# ESP181A.net
KiCad netlist of a schematic drawn in EAGLE
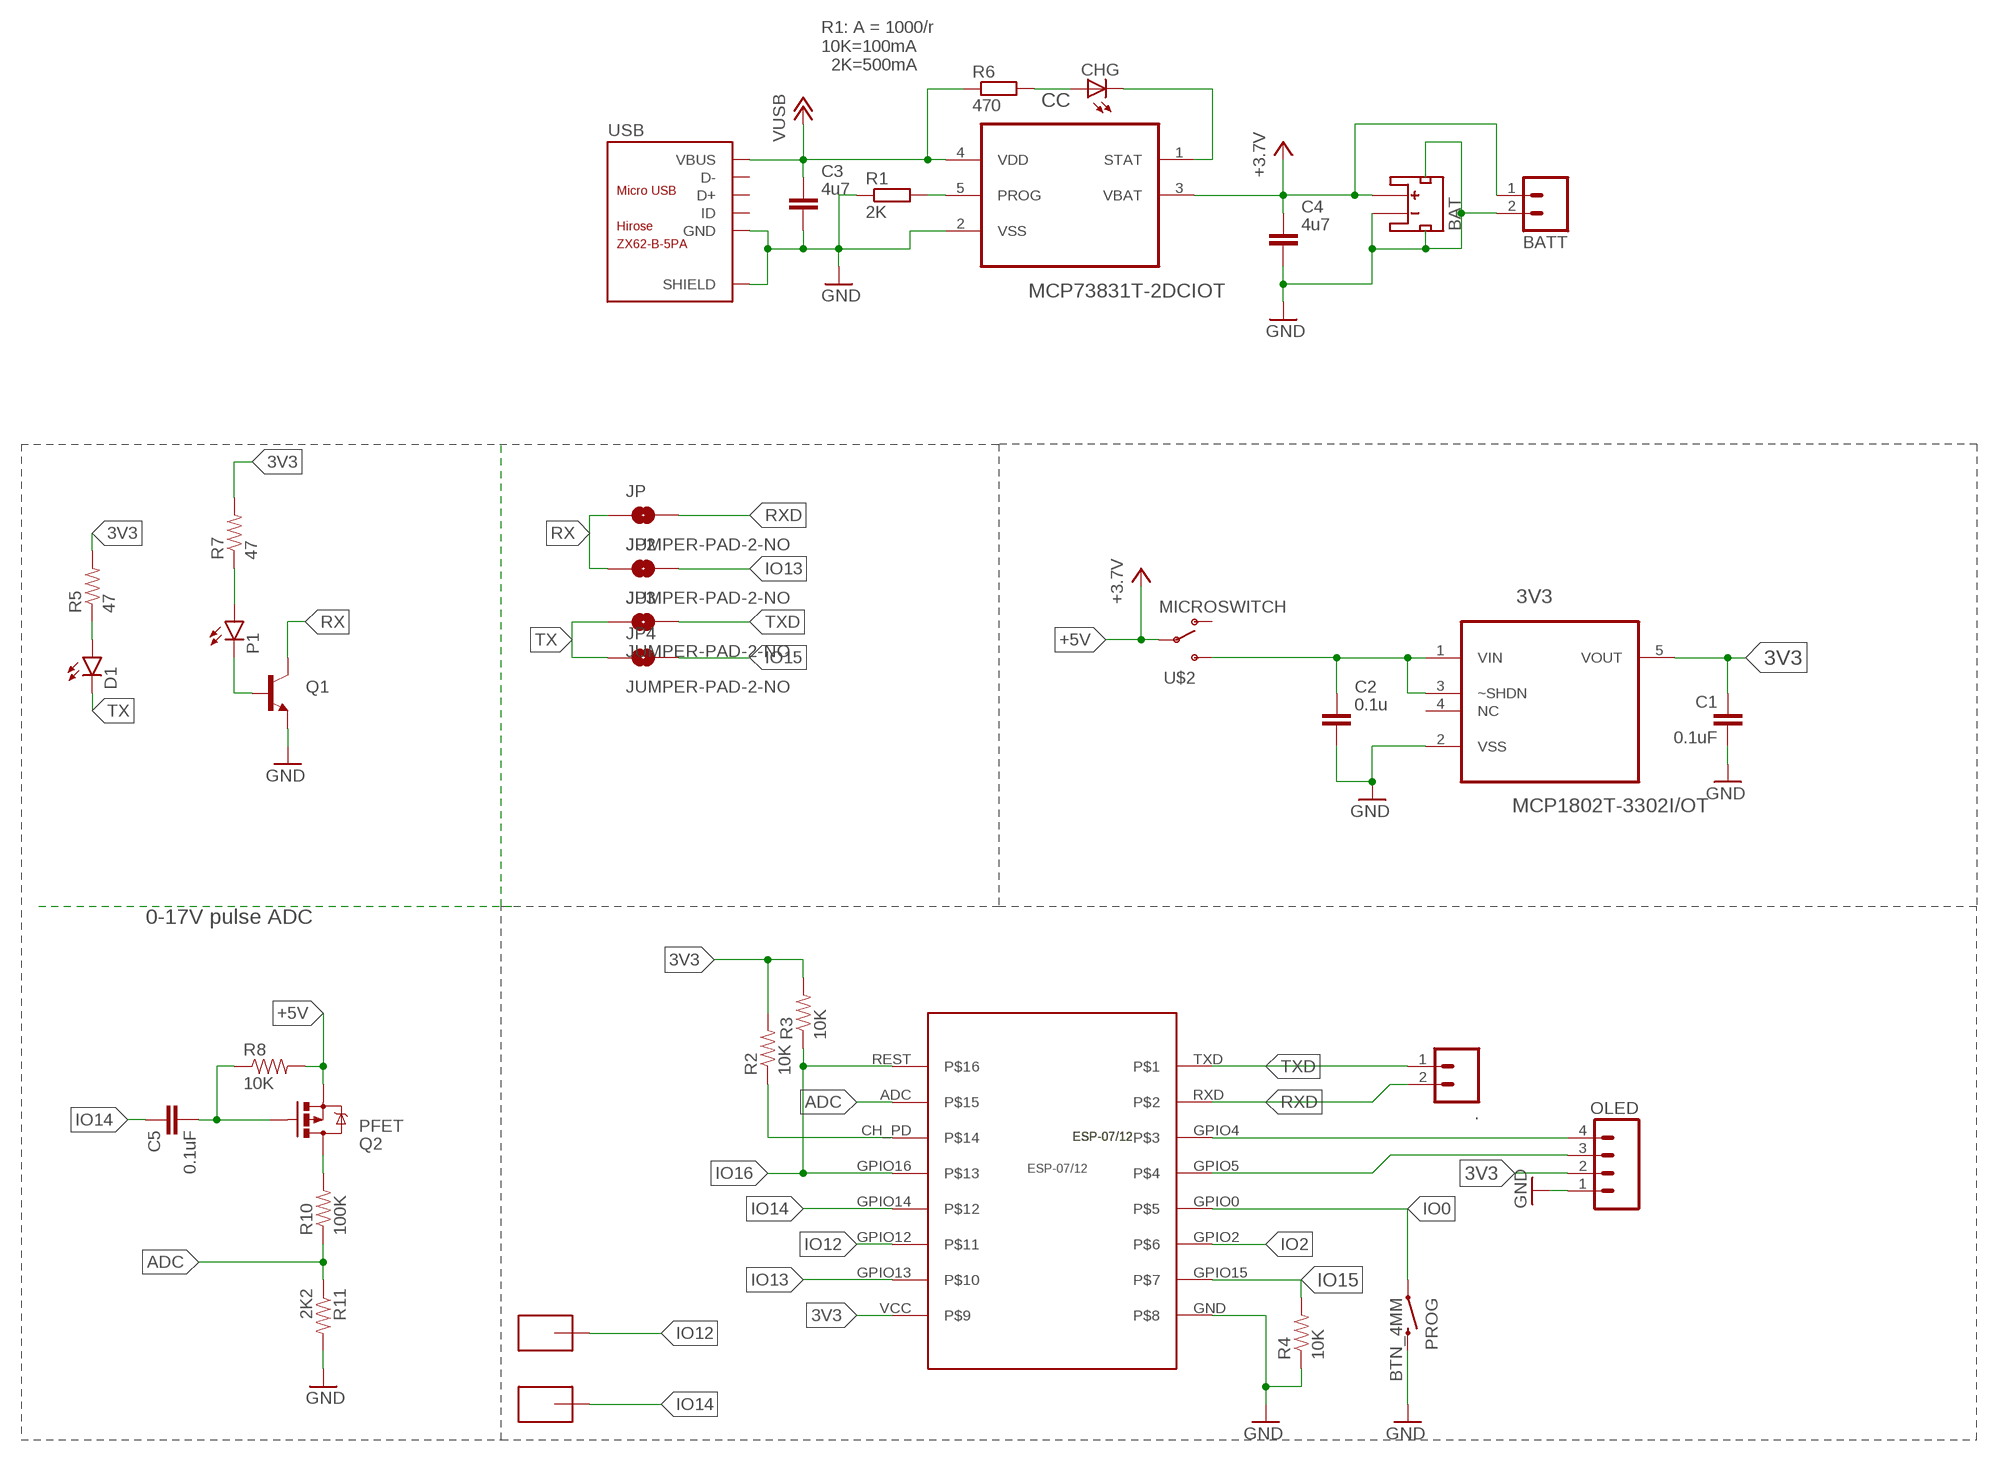
[diagram p0: schematic, sheet 1]

(export (version "E")
  (design (tool "Eeschema 10.0.6"))
  (components
    (comp (ref ".")
      (value "M02PTH")
      (footprint "eagle-import:1X02")
      (libsource (lib "eagle-import") (part "M02PTH"))
    )
    (comp (ref "3V3")
      (value "MCP1802T-3302I/OT")
      (footprint "eagle-import:SOT95P270X145-5N")
      (fields (field (name "MPN") "MCP1802T-3002I/OT"))
      (libsource (lib "eagle-import") (part "MCP1802T-3002I/OT"))
    )
    (comp (ref "BAT")
      (value "JST1.25MM")
      (footprint "eagle-import:JST_1.25MM")
      (libsource (lib "eagle-import") (part "JST1.25MM"))
    )
    (comp (ref "BATT")
      (value "M02PTH")
      (footprint "eagle-import:1X02")
      (libsource (lib "eagle-import") (part "M02PTH"))
    )
    (comp (ref "C1")
      (value "0.1uF")
      (footprint "eagle-import:0805-CAP")
      (libsource (lib "eagle-import") (part "CAP"))
    )
    (comp (ref "C2")
      (value "0.1u")
      (footprint "eagle-import:C603")
      (libsource (lib "eagle-import") (part "CAPACITOR_NPOL-0603"))
    )
    (comp (ref "C3")
      (value "4u7")
      (footprint "eagle-import:C603")
      (libsource (lib "eagle-import") (part "CAPACITOR_NPOL-0603"))
    )
    (comp (ref "C4")
      (value "4u7")
      (footprint "eagle-import:C603")
      (libsource (lib "eagle-import") (part "CAPACITOR_NPOL-0603"))
    )
    (comp (ref "C5")
      (value "0.1uF")
      (footprint "eagle-import:0805-CAP")
      (libsource (lib "eagle-import") (part "CAP"))
    )
    (comp (ref "CC")
      (value "MCP73831T-2DCIOT")
      (footprint "eagle-import:SOT95P280X145-5N")
      (fields (field (name "MPN") "MCP73832T-2ACI/OT"))
      (libsource (lib "eagle-import") (part "MCP73832T-2ACI/OT"))
    )
    (comp (ref "CHG")
      (value "LEDCHIP-LED0805")
      (footprint "eagle-import:CHIP-LED0805")
      (libsource (lib "eagle-import") (part "LEDCHIP-LED0805"))
    )
    (comp (ref "D1")
      (value "LED3MM")
      (footprint "eagle-import:LED3MM")
      (libsource (lib "eagle-import") (part "LED3MM"))
    )
    (comp (ref "JP")
      (value "JUMPER-PAD-2-NO")
      (footprint "eagle-import:PAD-JUMPER-2-NO_NO_SILK")
      (libsource (lib "eagle-import") (part "JUMPER-PAD-2-NO"))
    )
    (comp (ref "JP2")
      (value "JUMPER-PAD-2-NO")
      (footprint "eagle-import:PAD-JUMPER-2-NO_NO_SILK")
      (libsource (lib "eagle-import") (part "JUMPER-PAD-2-NO"))
    )
    (comp (ref "JP3")
      (value "JUMPER-PAD-2-NO")
      (footprint "eagle-import:PAD-JUMPER-2-NO_NO_SILK")
      (libsource (lib "eagle-import") (part "JUMPER-PAD-2-NO"))
    )
    (comp (ref "JP4")
      (value "JUMPER-PAD-2-NO")
      (footprint "eagle-import:PAD-JUMPER-2-NO_NO_SILK")
      (libsource (lib "eagle-import") (part "JUMPER-PAD-2-NO"))
    )
    (comp (ref "OLED")
      (value "M04PTH")
      (footprint "eagle-import:1X04")
      (libsource (lib "eagle-import") (part "M04PTH"))
    )
    (comp (ref "P1")
      (value "LED3MM")
      (footprint "eagle-import:LED3MM")
      (libsource (lib "eagle-import") (part "LED3MM"))
    )
    (comp (ref "PROG")
      (value "BTN_4MM")
      (footprint "eagle-import:BTN_4MM")
      (libsource (lib "eagle-import") (part "BTN_4MM"))
    )
    (comp (ref "Q1")
      (value "TRANSISTOR_NPNSOT23-3")
      (footprint "eagle-import:SOT23-3")
      (libsource (lib "eagle-import") (part "TRANSISTOR_NPNSOT23-3"))
    )
    (comp (ref "Q2")
      (value "PFET")
      (footprint "eagle-import:SOT23-3")
      (libsource (lib "eagle-import") (part "MOSFET-PCHANNEL"))
    )
    (comp (ref "R1")
      (value "2K")
      (footprint "eagle-import:R603")
      (libsource (lib "eagle-import") (part "RESISTOR-0603"))
    )
    (comp (ref "R2")
      (value "10K")
      (footprint "eagle-import:0805")
      (libsource (lib "eagle-import") (part "RESISTOR0805-RES"))
    )
    (comp (ref "R3")
      (value "10K")
      (footprint "eagle-import:0805")
      (libsource (lib "eagle-import") (part "RESISTOR0805-RES"))
    )
    (comp (ref "R4")
      (value "10K")
      (footprint "eagle-import:0805")
      (libsource (lib "eagle-import") (part "RESISTOR0805-RES"))
    )
    (comp (ref "R5")
      (value "47")
      (footprint "eagle-import:0805")
      (libsource (lib "eagle-import") (part "RESISTOR0805-RES"))
    )
    (comp (ref "R6")
      (value "470")
      (footprint "eagle-import:R603")
      (libsource (lib "eagle-import") (part "RESISTOR-0603"))
    )
    (comp (ref "R7")
      (value "47")
      (footprint "eagle-import:0805")
      (libsource (lib "eagle-import") (part "RESISTOR0805-RES"))
    )
    (comp (ref "R8")
      (value "10K")
      (footprint "eagle-import:0805")
      (libsource (lib "eagle-import") (part "RESISTOR0805-RES"))
    )
    (comp (ref "R10")
      (value "100K")
      (footprint "eagle-import:0805")
      (libsource (lib "eagle-import") (part "RESISTOR0805-RES"))
    )
    (comp (ref "R11")
      (value "2K2")
      (footprint "eagle-import:0805")
      (libsource (lib "eagle-import") (part "RESISTOR0805-RES"))
    )
    (comp (ref "U$1")
      (value "ESP-07/12")
      (footprint "eagle-import:ESP-07_12")
      (libsource (lib "eagle-import") (part "ESP-07/12"))
    )
    (comp (ref "U$2")
      (value "MICROSWITCH")
      (footprint "eagle-import:MICROSWITCH")
      (libsource (lib "eagle-import") (part "MICROSWITCH"))
    )
    (comp (ref "U$3")
      (value "SMD-PAD182X64")
      (footprint "eagle-import:SMD-PAD1")
      (libsource (lib "eagle-import") (part "SMD-PAD182X64"))
    )
    (comp (ref "U$4")
      (value "SMD-PAD182X64")
      (footprint "eagle-import:SMD-PAD1")
      (libsource (lib "eagle-import") (part "SMD-PAD182X64"))
    )
    (comp (ref "USB")
      (value "ZX62-B-5PA")
      (footprint "eagle-import:MICRO-USB5+6P-SMD-0.65-AB")
      (libsource (lib "eagle-import") (part "MICRO-USB-SMD(ZX62-B-5PA)"))
    )
  )
  (nets
    (net (code "1") (name "+5V") (class "Default")
      (node (ref "BAT") (pin "2") (pinfunction "+_2") (pintype "bidirectional"))
      (node (ref "BATT") (pin "1") (pinfunction "1_1") (pintype "passive"))
      (node (ref "C4") (pin "1") (pinfunction "1_1") (pintype "passive"))
      (node (ref "CC") (pin "3") (pinfunction "VBAT_3") (pintype "output"))
      (node (ref "Q2") (pin "2") (pinfunction "S_2") (pintype "passive"))
      (node (ref "R8") (pin "2") (pinfunction "2_2") (pintype "passive"))
      (node (ref "U$2") (pin "2") (pinfunction "P_2") (pintype "passive"))
    )
    (net (code "2") (name "3V3") (class "Default")
      (node (ref "3V3") (pin "5") (pinfunction "VOUT_5") (pintype "output"))
      (node (ref "C1") (pin "1") (pinfunction "1_1") (pintype "passive"))
      (node (ref "OLED") (pin "2") (pinfunction "2_2") (pintype "passive"))
      (node (ref "R2") (pin "2") (pinfunction "2_2") (pintype "passive"))
      (node (ref "R3") (pin "2") (pinfunction "2_2") (pintype "passive"))
      (node (ref "R5") (pin "2") (pinfunction "2_2") (pintype "passive"))
      (node (ref "R7") (pin "2") (pinfunction "2_2") (pintype "passive"))
      (node (ref "U$1") (pin "VCC") (pinfunction "P$9_VCC") (pintype "bidirectional"))
    )
    (net (code "3") (name "ADC") (class "Default")
      (node (ref "R10") (pin "1") (pinfunction "1_1") (pintype "passive"))
      (node (ref "R11") (pin "1") (pinfunction "1_1") (pintype "passive"))
      (node (ref "U$1") (pin "ADC") (pinfunction "P$15_ADC") (pintype "bidirectional"))
    )
    (net (code "4") (name "GND") (class "Default")
      (node (ref "3V3") (pin "2") (pinfunction "VSS_2") (pintype "passive"))
      (node (ref "BAT") (pin "1") (pinfunction "-_1") (pintype "bidirectional"))
      (node (ref "BAT") (pin "NC1") (pinfunction "PAD1_NC1") (pintype "bidirectional"))
      (node (ref "BAT") (pin "NC2") (pinfunction "PAD2_NC2") (pintype "bidirectional"))
      (node (ref "BATT") (pin "2") (pinfunction "2_2") (pintype "passive"))
      (node (ref "C1") (pin "2") (pinfunction "2_2") (pintype "passive"))
      (node (ref "C2") (pin "2") (pinfunction "2_2") (pintype "passive"))
      (node (ref "C3") (pin "2") (pinfunction "2_2") (pintype "passive"))
      (node (ref "C4") (pin "2") (pinfunction "2_2") (pintype "passive"))
      (node (ref "CC") (pin "2") (pinfunction "VSS_2") (pintype "power_in"))
      (node (ref "OLED") (pin "1") (pinfunction "1_1") (pintype "passive"))
      (node (ref "PROG") (pin "2") (pinfunction "2_2") (pintype "passive"))
      (node (ref "Q1") (pin "2") (pinfunction "E_2") (pintype "passive"))
      (node (ref "R1") (pin "1") (pinfunction "1_1") (pintype "passive"))
      (node (ref "R11") (pin "2") (pinfunction "2_2") (pintype "passive"))
      (node (ref "R4") (pin "1") (pinfunction "1_1") (pintype "passive"))
      (node (ref "U$1") (pin "GND") (pinfunction "P$8_GND") (pintype "bidirectional"))
      (node (ref "USB") (pin "5") (pinfunction "GND_5") (pintype "power_in"))
      (node (ref "USB") (pin "P1") (pinfunction "SHIELD_P1") (pintype "power_in"))
      (node (ref "USB") (pin "P2") (pinfunction "SHIELD_P2") (pintype "power_in"))
      (node (ref "USB") (pin "P3") (pinfunction "SHIELD_P3") (pintype "power_in"))
      (node (ref "USB") (pin "P4") (pinfunction "SHIELD_P4") (pintype "power_in"))
      (node (ref "USB") (pin "P5") (pinfunction "SHIELD_P5") (pintype "power_in"))
      (node (ref "USB") (pin "P6") (pinfunction "SHIELD_P6") (pintype "power_in"))
    )
    (net (code "5") (name "IO0") (class "Default")
      (node (ref "PROG") (pin "1") (pinfunction "1_1") (pintype "passive"))
      (node (ref "U$1") (pin "GPIO0") (pinfunction "P$5_GPIO0") (pintype "bidirectional"))
    )
    (net (code "6") (name "IO2") (class "Default")
      (node (ref "U$1") (pin "GPIO2") (pinfunction "P$6_GPIO2") (pintype "bidirectional"))
    )
    (net (code "7") (name "IO12") (class "Default")
      (node (ref "U$1") (pin "GPIO12") (pinfunction "P$11_GPIO12") (pintype "bidirectional"))
      (node (ref "U$4") (pin ">PAD") (pinfunction "P$1_>PAD") (pintype "bidirectional"))
    )
    (net (code "8") (name "IO13") (class "Default")
      (node (ref "JP2") (pin "2") (pinfunction "2_2") (pintype "passive"))
      (node (ref "U$1") (pin "GPIO13") (pinfunction "P$10_GPIO13") (pintype "bidirectional"))
    )
    (net (code "9") (name "IO14") (class "Default")
      (node (ref "C5") (pin "1") (pinfunction "1_1") (pintype "passive"))
      (node (ref "U$1") (pin "GPIO14") (pinfunction "P$12_GPIO14") (pintype "bidirectional"))
      (node (ref "U$3") (pin ">PAD") (pinfunction "P$1_>PAD") (pintype "bidirectional"))
    )
    (net (code "10") (name "IO15") (class "Default")
      (node (ref "JP4") (pin "2") (pinfunction "2_2") (pintype "passive"))
      (node (ref "R4") (pin "2") (pinfunction "2_2") (pintype "passive"))
      (node (ref "U$1") (pin "GPIO15") (pinfunction "P$7_GPIO15") (pintype "bidirectional"))
    )
    (net (code "11") (name "IO16") (class "Default")
      (node (ref "R3") (pin "1") (pinfunction "1_1") (pintype "passive"))
      (node (ref "U$1") (pin "GPIO16") (pinfunction "P$13_GPIO16") (pintype "bidirectional"))
      (node (ref "U$1") (pin "REST") (pinfunction "P$16_REST") (pintype "bidirectional"))
    )
    (net (code "12") (name "Net-(3V3-VIN)") (class "Default")
      (node (ref "3V3") (pin "1") (pinfunction "VIN_1") (pintype "power_in"))
      (node (ref "3V3") (pin "3") (pinfunction "~{SHDN}_3") (pintype "input"))
      (node (ref "C2") (pin "1") (pinfunction "1_1") (pintype "passive"))
      (node (ref "U$2") (pin "3") (pinfunction "S_3") (pintype "passive"))
    )
    (net (code "13") (name "Net-(CC-PROG)") (class "Default")
      (node (ref "CC") (pin "5") (pinfunction "PROG_5") (pintype "input"))
      (node (ref "R1") (pin "2") (pinfunction "2_2") (pintype "passive"))
    )
    (net (code "14") (name "Net-(CC-STAT)") (class "Default")
      (node (ref "CC") (pin "1") (pinfunction "STAT_1") (pintype "output"))
      (node (ref "CHG") (pin "C") (pinfunction "C_C") (pintype "passive"))
    )
    (net (code "15") (name "Net-(CHG-PadA)") (class "Default")
      (node (ref "CHG") (pin "A") (pinfunction "A_A") (pintype "passive"))
      (node (ref "R6") (pin "2") (pinfunction "2_2") (pintype "passive"))
    )
    (net (code "16") (name "Net-(D1-PadA)") (class "Default")
      (node (ref "D1") (pin "A") (pinfunction "A_A") (pintype "passive"))
      (node (ref "R5") (pin "1") (pinfunction "1_1") (pintype "passive"))
    )
    (net (code "17") (name "Net-(P1-C)") (class "Default")
      (node (ref "P1") (pin "K") (pinfunction "C_K") (pintype "passive"))
      (node (ref "Q1") (pin "1") (pinfunction "B_1") (pintype "passive"))
    )
    (net (code "18") (name "Net-(P1-PadA)") (class "Default")
      (node (ref "P1") (pin "A") (pinfunction "A_A") (pintype "passive"))
      (node (ref "R7") (pin "1") (pinfunction "1_1") (pintype "passive"))
    )
    (net (code "19") (name "Net-(Q2-D)") (class "Default")
      (node (ref "Q2") (pin "3") (pinfunction "D_3") (pintype "passive"))
      (node (ref "R10") (pin "2") (pinfunction "2_2") (pintype "passive"))
    )
    (net (code "20") (name "Net-(Q2-G)") (class "Default")
      (node (ref "C5") (pin "2") (pinfunction "2_2") (pintype "passive"))
      (node (ref "Q2") (pin "1") (pinfunction "G_1") (pintype "passive"))
      (node (ref "R8") (pin "1") (pinfunction "1_1") (pintype "passive"))
    )
    (net (code "21") (name "Net-(U$1-P$3)") (class "Default")
      (node (ref "OLED") (pin "4") (pinfunction "4_4") (pintype "passive"))
      (node (ref "U$1") (pin "GPIO4") (pinfunction "P$3_GPIO4") (pintype "bidirectional"))
    )
    (net (code "22") (name "Net-(U$1-P$4)") (class "Default")
      (node (ref "OLED") (pin "3") (pinfunction "3_3") (pintype "passive"))
      (node (ref "U$1") (pin "GPIO5") (pinfunction "P$4_GPIO5") (pintype "bidirectional"))
    )
    (net (code "23") (name "Net-(U$1-P$14)") (class "Default")
      (node (ref "R2") (pin "1") (pinfunction "1_1") (pintype "passive"))
      (node (ref "U$1") (pin "CH_PD") (pinfunction "P$14_CH_PD") (pintype "bidirectional"))
    )
    (net (code "24") (name "RX") (class "Default")
      (node (ref "JP") (pin "1") (pinfunction "1_1") (pintype "passive"))
      (node (ref "JP2") (pin "1") (pinfunction "1_1") (pintype "passive"))
      (node (ref "Q1") (pin "3") (pinfunction "C_3") (pintype "passive"))
    )
    (net (code "25") (name "RXD") (class "Default")
      (node (ref ".") (pin "2") (pinfunction "2_2") (pintype "passive"))
      (node (ref "JP") (pin "2") (pinfunction "2_2") (pintype "passive"))
      (node (ref "U$1") (pin "RXD") (pinfunction "P$2_RXD") (pintype "bidirectional"))
    )
    (net (code "26") (name "TX") (class "Default")
      (node (ref "D1") (pin "K") (pinfunction "C_K") (pintype "passive"))
      (node (ref "JP3") (pin "1") (pinfunction "1_1") (pintype "passive"))
      (node (ref "JP4") (pin "1") (pinfunction "1_1") (pintype "passive"))
    )
    (net (code "27") (name "TXD") (class "Default")
      (node (ref ".") (pin "1") (pinfunction "1_1") (pintype "passive"))
      (node (ref "JP3") (pin "2") (pinfunction "2_2") (pintype "passive"))
      (node (ref "U$1") (pin "TXD") (pinfunction "P$1_TXD") (pintype "bidirectional"))
    )
    (net (code "28") (name "VUSB") (class "Default")
      (node (ref "C3") (pin "1") (pinfunction "1_1") (pintype "passive"))
      (node (ref "CC") (pin "4") (pinfunction "VDD_4") (pintype "power_in"))
      (node (ref "R6") (pin "1") (pinfunction "1_1") (pintype "passive"))
      (node (ref "USB") (pin "1") (pinfunction "VBUS_1") (pintype "power_in"))
    )
    (net (code "29") (name "unconnected-(3V3-NC-Pad4)") (class "Default")
      (node (ref "3V3") (pin "4") (pinfunction "NC_4") (pintype "no_connect"))
    )
    (net (code "30") (name "unconnected-(U$2-O-Pad1)") (class "Default")
      (node (ref "U$2") (pin "1") (pinfunction "O_1") (pintype "passive"))
    )
    (net (code "31") (name "unconnected-(USB-D+-Pad3)") (class "Default")
      (node (ref "USB") (pin "3") (pinfunction "D+_3") (pintype "bidirectional"))
    )
    (net (code "32") (name "unconnected-(USB-D--Pad2)") (class "Default")
      (node (ref "USB") (pin "2") (pinfunction "D-_2") (pintype "bidirectional"))
    )
    (net (code "33") (name "unconnected-(USB-ID-Pad4)") (class "Default")
      (node (ref "USB") (pin "4") (pinfunction "ID_4") (pintype "bidirectional"))
    )
  )
)
